# center.net
KiCad netlist of a schematic drawn in EAGLE
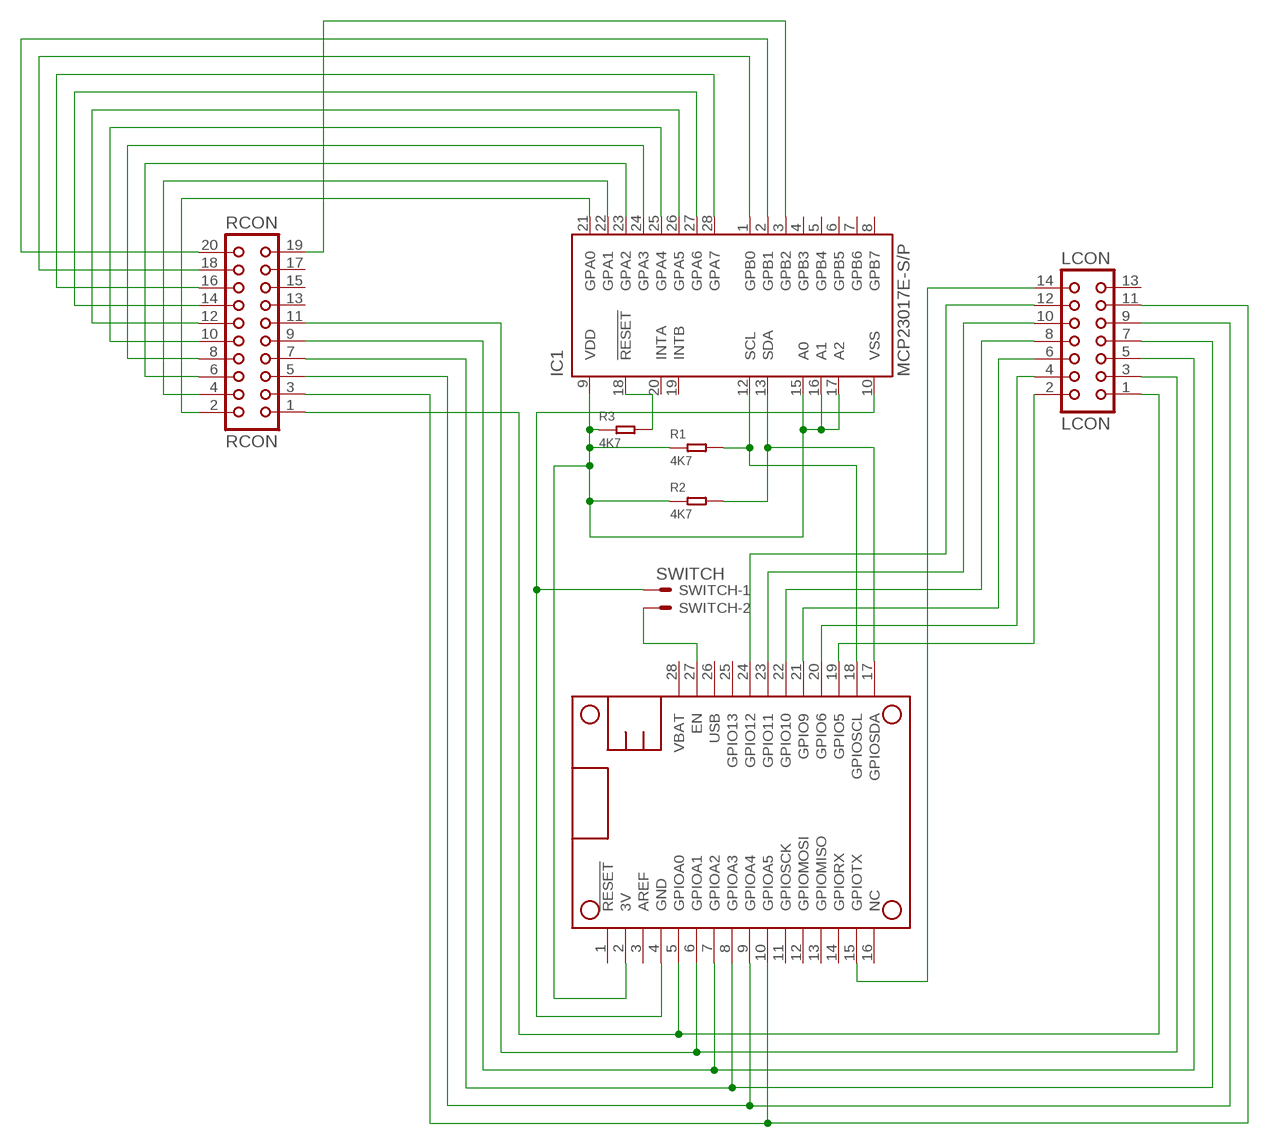
[diagram p0: schematic, sheet 1]

(export (version "E")
  (design (tool "Eeschema 10.0.6"))
  (components
    (comp (ref "IC1")
      (value "MCP23017E-S/P")
      (footprint "eagle-import:DIL28-3")
      (libsource (lib "eagle-import") (part "MCP23017SP"))
    )
    (comp (ref "LCON")
      (value "LCON")
      (footprint "eagle-import:CON14")
      (libsource (lib "eagle-import") (part "CON14"))
    )
    (comp (ref "MS1")
      (value "FEATHERWING_NODIM")
      (footprint "eagle-import:FEATHERWING_DIM")
      (libsource (lib "eagle-import") (part "FEATHERWING_NODIM"))
    )
    (comp (ref "R1")
      (value "4K7")
      (footprint "eagle-import:PR-D2.3XL6.5MM")
      (fields (field (name "MPN") "FHCFR-1/4W-472J"))
      (libsource (lib "eagle-import") (part "DIP-RES-4.7K-5%-1/4W(PR-D2.3XL6.5MM)"))
    )
    (comp (ref "R2")
      (value "4K7")
      (footprint "eagle-import:PR-D2.3XL6.5MM")
      (fields (field (name "MPN") "FHCFR-1/4W-472J"))
      (libsource (lib "eagle-import") (part "DIP-RES-4.7K-5%-1/4W(PR-D2.3XL6.5MM)"))
    )
    (comp (ref "R3")
      (value "4K7")
      (footprint "eagle-import:PR-D2.3XL6.5MM")
      (fields (field (name "MPN") "FHCFR-1/4W-472J"))
      (libsource (lib "eagle-import") (part "DIP-RES-4.7K-5%-1/4W(PR-D2.3XL6.5MM)"))
    )
    (comp (ref "RCON")
      (value "RCON")
      (footprint "eagle-import:CON20")
      (libsource (lib "eagle-import") (part "CON20"))
    )
    (comp (ref "SWITCH")
      (value "SWITCH")
      (footprint "eagle-import:JST-XH-02-PACKAGE-LONG-PAD")
      (libsource (lib "eagle-import") (part "JST-XH-02-PIN-LONG-PAD"))
    )
  )
  (nets
    (net (code "1") (name "/USB") (class "Default")
      (node (ref "MS1") (pin "26") (pinfunction "USB_26") (pintype "power_in"))
    )
    (net (code "2") (name "/VBAT") (class "Default")
      (node (ref "MS1") (pin "28") (pinfunction "VBAT_28") (pintype "power_in"))
    )
    (net (code "3") (name "Net-(IC1-A0)") (class "Default")
      (node (ref "IC1") (pin "15") (pinfunction "A0_15") (pintype "input"))
      (node (ref "IC1") (pin "16") (pinfunction "A1_16") (pintype "input"))
      (node (ref "IC1") (pin "17") (pinfunction "A2_17") (pintype "input"))
      (node (ref "IC1") (pin "9") (pinfunction "VDD_9") (pintype "power_in"))
      (node (ref "MS1") (pin "2") (pinfunction "3V_2") (pintype "power_in"))
      (node (ref "R1") (pin "1") (pinfunction "1_1") (pintype "passive"))
      (node (ref "R2") (pin "1") (pinfunction "1_1") (pintype "passive"))
      (node (ref "R3") (pin "1") (pinfunction "1_1") (pintype "passive"))
    )
    (net (code "4") (name "Net-(IC1-GPA0)") (class "Default")
      (node (ref "IC1") (pin "21") (pinfunction "GPA0_21") (pintype "bidirectional"))
      (node (ref "RCON") (pin "2") (pinfunction "2_2") (pintype "passive"))
    )
    (net (code "5") (name "Net-(IC1-GPA1)") (class "Default")
      (node (ref "IC1") (pin "22") (pinfunction "GPA1_22") (pintype "bidirectional"))
      (node (ref "RCON") (pin "4") (pinfunction "4_4") (pintype "passive"))
    )
    (net (code "6") (name "Net-(IC1-GPA2)") (class "Default")
      (node (ref "IC1") (pin "23") (pinfunction "GPA2_23") (pintype "bidirectional"))
      (node (ref "RCON") (pin "6") (pinfunction "6_6") (pintype "passive"))
    )
    (net (code "7") (name "Net-(IC1-GPA3)") (class "Default")
      (node (ref "IC1") (pin "24") (pinfunction "GPA3_24") (pintype "bidirectional"))
      (node (ref "RCON") (pin "8") (pinfunction "8_8") (pintype "passive"))
    )
    (net (code "8") (name "Net-(IC1-GPA4)") (class "Default")
      (node (ref "IC1") (pin "25") (pinfunction "GPA4_25") (pintype "bidirectional"))
      (node (ref "RCON") (pin "10") (pinfunction "10_10") (pintype "passive"))
    )
    (net (code "9") (name "Net-(IC1-GPA5)") (class "Default")
      (node (ref "IC1") (pin "26") (pinfunction "GPA5_26") (pintype "bidirectional"))
      (node (ref "RCON") (pin "12") (pinfunction "12_12") (pintype "passive"))
    )
    (net (code "10") (name "Net-(IC1-GPA6)") (class "Default")
      (node (ref "IC1") (pin "27") (pinfunction "GPA6_27") (pintype "bidirectional"))
      (node (ref "RCON") (pin "14") (pinfunction "14_14") (pintype "passive"))
    )
    (net (code "11") (name "Net-(IC1-GPA7)") (class "Default")
      (node (ref "IC1") (pin "28") (pinfunction "GPA7_28") (pintype "bidirectional"))
      (node (ref "RCON") (pin "16") (pinfunction "16_16") (pintype "passive"))
    )
    (net (code "12") (name "Net-(IC1-GPB0)") (class "Default")
      (node (ref "IC1") (pin "1") (pinfunction "GPB0_1") (pintype "bidirectional"))
      (node (ref "RCON") (pin "18") (pinfunction "18_18") (pintype "passive"))
    )
    (net (code "13") (name "Net-(IC1-GPB1)") (class "Default")
      (node (ref "IC1") (pin "2") (pinfunction "GPB1_2") (pintype "bidirectional"))
      (node (ref "RCON") (pin "20") (pinfunction "20_20") (pintype "passive"))
    )
    (net (code "14") (name "Net-(IC1-GPB2)") (class "Default")
      (node (ref "IC1") (pin "3") (pinfunction "GPB2_3") (pintype "bidirectional"))
      (node (ref "RCON") (pin "19") (pinfunction "19_19") (pintype "passive"))
    )
    (net (code "15") (name "Net-(IC1-SCL)") (class "Default")
      (node (ref "IC1") (pin "12") (pinfunction "SCL_12") (pintype "input"))
      (node (ref "MS1") (pin "18") (pinfunction "GPIOSCL_18") (pintype "bidirectional"))
      (node (ref "R1") (pin "2") (pinfunction "2_2") (pintype "passive"))
    )
    (net (code "16") (name "Net-(IC1-SDA)") (class "Default")
      (node (ref "IC1") (pin "13") (pinfunction "SDA_13") (pintype "bidirectional"))
      (node (ref "MS1") (pin "17") (pinfunction "GPIOSDA_17") (pintype "bidirectional"))
      (node (ref "R2") (pin "2") (pinfunction "2_2") (pintype "passive"))
    )
    (net (code "17") (name "Net-(IC1-VSS)") (class "Default")
      (node (ref "IC1") (pin "10") (pinfunction "VSS_10") (pintype "power_in"))
      (node (ref "MS1") (pin "4") (pinfunction "GND_4") (pintype "power_in"))
      (node (ref "SWITCH") (pin "1") (pinfunction "S_1") (pintype "passive"))
    )
    (net (code "18") (name "Net-(IC1-~{RESET})") (class "Default")
      (node (ref "IC1") (pin "18") (pinfunction "~{RESET}_18") (pintype "input"))
      (node (ref "R3") (pin "2") (pinfunction "2_2") (pintype "passive"))
    )
    (net (code "19") (name "Net-(MS1-EN)") (class "Default")
      (node (ref "MS1") (pin "27") (pinfunction "EN_27") (pintype "passive"))
      (node (ref "SWITCH") (pin "2") (pinfunction "S_2") (pintype "passive"))
    )
    (net (code "20") (name "Net-(MS1-GPIO5)") (class "Default")
      (node (ref "LCON") (pin "2") (pinfunction "2_2") (pintype "passive"))
      (node (ref "MS1") (pin "19") (pinfunction "GPIO5_19") (pintype "bidirectional"))
    )
    (net (code "21") (name "Net-(MS1-GPIO6)") (class "Default")
      (node (ref "LCON") (pin "4") (pinfunction "4_4") (pintype "passive"))
      (node (ref "MS1") (pin "20") (pinfunction "GPIO6_20") (pintype "bidirectional"))
    )
    (net (code "22") (name "Net-(MS1-GPIO9)") (class "Default")
      (node (ref "LCON") (pin "6") (pinfunction "6_6") (pintype "passive"))
      (node (ref "MS1") (pin "21") (pinfunction "GPIO9_21") (pintype "bidirectional"))
    )
    (net (code "23") (name "Net-(MS1-GPIO10)") (class "Default")
      (node (ref "LCON") (pin "8") (pinfunction "8_8") (pintype "passive"))
      (node (ref "MS1") (pin "22") (pinfunction "GPIO10_22") (pintype "bidirectional"))
    )
    (net (code "24") (name "Net-(MS1-GPIO11)") (class "Default")
      (node (ref "LCON") (pin "10") (pinfunction "10_10") (pintype "passive"))
      (node (ref "MS1") (pin "23") (pinfunction "GPIO11_23") (pintype "bidirectional"))
    )
    (net (code "25") (name "Net-(MS1-GPIO12)") (class "Default")
      (node (ref "LCON") (pin "12") (pinfunction "12_12") (pintype "passive"))
      (node (ref "MS1") (pin "24") (pinfunction "GPIO12_24") (pintype "bidirectional"))
    )
    (net (code "26") (name "Net-(MS1-GPIOA0)") (class "Default")
      (node (ref "LCON") (pin "1") (pinfunction "1_1") (pintype "passive"))
      (node (ref "MS1") (pin "5") (pinfunction "GPIOA0_5") (pintype "bidirectional"))
      (node (ref "RCON") (pin "1") (pinfunction "1_1") (pintype "passive"))
    )
    (net (code "27") (name "Net-(MS1-GPIOA1)") (class "Default")
      (node (ref "LCON") (pin "3") (pinfunction "3_3") (pintype "passive"))
      (node (ref "MS1") (pin "6") (pinfunction "GPIOA1_6") (pintype "bidirectional"))
      (node (ref "RCON") (pin "11") (pinfunction "11_11") (pintype "passive"))
    )
    (net (code "28") (name "Net-(MS1-GPIOA2)") (class "Default")
      (node (ref "LCON") (pin "5") (pinfunction "5_5") (pintype "passive"))
      (node (ref "MS1") (pin "7") (pinfunction "GPIOA2_7") (pintype "bidirectional"))
      (node (ref "RCON") (pin "9") (pinfunction "9_9") (pintype "passive"))
    )
    (net (code "29") (name "Net-(MS1-GPIOA3)") (class "Default")
      (node (ref "LCON") (pin "7") (pinfunction "7_7") (pintype "passive"))
      (node (ref "MS1") (pin "8") (pinfunction "GPIOA3_8") (pintype "bidirectional"))
      (node (ref "RCON") (pin "7") (pinfunction "7_7") (pintype "passive"))
    )
    (net (code "30") (name "Net-(MS1-GPIOA4)") (class "Default")
      (node (ref "LCON") (pin "9") (pinfunction "9_9") (pintype "passive"))
      (node (ref "MS1") (pin "9") (pinfunction "GPIOA4_9") (pintype "bidirectional"))
      (node (ref "RCON") (pin "5") (pinfunction "5_5") (pintype "passive"))
    )
    (net (code "31") (name "Net-(MS1-GPIOA5)") (class "Default")
      (node (ref "LCON") (pin "11") (pinfunction "11_11") (pintype "passive"))
      (node (ref "MS1") (pin "10") (pinfunction "GPIOA5_10") (pintype "bidirectional"))
      (node (ref "RCON") (pin "3") (pinfunction "3_3") (pintype "passive"))
    )
    (net (code "32") (name "Net-(MS1-GPIOTX)") (class "Default")
      (node (ref "LCON") (pin "14") (pinfunction "14_14") (pintype "passive"))
      (node (ref "MS1") (pin "15") (pinfunction "GPIOTX_15") (pintype "bidirectional"))
    )
    (net (code "33") (name "unconnected-(IC1-GPB3-Pad4)") (class "Default")
      (node (ref "IC1") (pin "4") (pinfunction "GPB3_4") (pintype "bidirectional"))
    )
    (net (code "34") (name "unconnected-(IC1-GPB4-Pad5)") (class "Default")
      (node (ref "IC1") (pin "5") (pinfunction "GPB4_5") (pintype "bidirectional"))
    )
    (net (code "35") (name "unconnected-(IC1-GPB5-Pad6)") (class "Default")
      (node (ref "IC1") (pin "6") (pinfunction "GPB5_6") (pintype "bidirectional"))
    )
    (net (code "36") (name "unconnected-(IC1-GPB6-Pad7)") (class "Default")
      (node (ref "IC1") (pin "7") (pinfunction "GPB6_7") (pintype "bidirectional"))
    )
    (net (code "37") (name "unconnected-(IC1-GPB7-Pad8)") (class "Default")
      (node (ref "IC1") (pin "8") (pinfunction "GPB7_8") (pintype "bidirectional"))
    )
    (net (code "38") (name "unconnected-(IC1-INTA-Pad20)") (class "Default")
      (node (ref "IC1") (pin "20") (pinfunction "INTA_20") (pintype "output"))
    )
    (net (code "39") (name "unconnected-(IC1-INTB-Pad19)") (class "Default")
      (node (ref "IC1") (pin "19") (pinfunction "INTB_19") (pintype "output"))
    )
    (net (code "40") (name "unconnected-(LCON-Pad13)") (class "Default")
      (node (ref "LCON") (pin "13") (pinfunction "13_13") (pintype "passive"))
    )
    (net (code "41") (name "unconnected-(MS1-AREF-Pad3)") (class "Default")
      (node (ref "MS1") (pin "3") (pinfunction "AREF_3") (pintype "passive"))
    )
    (net (code "42") (name "unconnected-(MS1-GPIO13-Pad25)") (class "Default")
      (node (ref "MS1") (pin "25") (pinfunction "GPIO13_25") (pintype "bidirectional"))
    )
    (net (code "43") (name "unconnected-(MS1-GPIOMISO-Pad13)") (class "Default")
      (node (ref "MS1") (pin "13") (pinfunction "GPIOMISO_13") (pintype "bidirectional"))
    )
    (net (code "44") (name "unconnected-(MS1-GPIOMOSI-Pad12)") (class "Default")
      (node (ref "MS1") (pin "12") (pinfunction "GPIOMOSI_12") (pintype "bidirectional"))
    )
    (net (code "45") (name "unconnected-(MS1-GPIORX-Pad14)") (class "Default")
      (node (ref "MS1") (pin "14") (pinfunction "GPIORX_14") (pintype "bidirectional"))
    )
    (net (code "46") (name "unconnected-(MS1-GPIOSCK-Pad11)") (class "Default")
      (node (ref "MS1") (pin "11") (pinfunction "GPIOSCK_11") (pintype "bidirectional"))
    )
    (net (code "47") (name "unconnected-(MS1-NC-Pad16)") (class "Default")
      (node (ref "MS1") (pin "16") (pinfunction "NC_16") (pintype "passive"))
    )
    (net (code "48") (name "unconnected-(MS1-~{RESET}-Pad1)") (class "Default")
      (node (ref "MS1") (pin "1") (pinfunction "~{RESET}_1") (pintype "input"))
    )
    (net (code "49") (name "unconnected-(RCON-Pad13)") (class "Default")
      (node (ref "RCON") (pin "13") (pinfunction "13_13") (pintype "passive"))
    )
    (net (code "50") (name "unconnected-(RCON-Pad15)") (class "Default")
      (node (ref "RCON") (pin "15") (pinfunction "15_15") (pintype "passive"))
    )
    (net (code "51") (name "unconnected-(RCON-Pad17)") (class "Default")
      (node (ref "RCON") (pin "17") (pinfunction "17_17") (pintype "passive"))
    )
  )
)
